# CC2530.net
KiCad netlist of a schematic drawn in Altium Designer
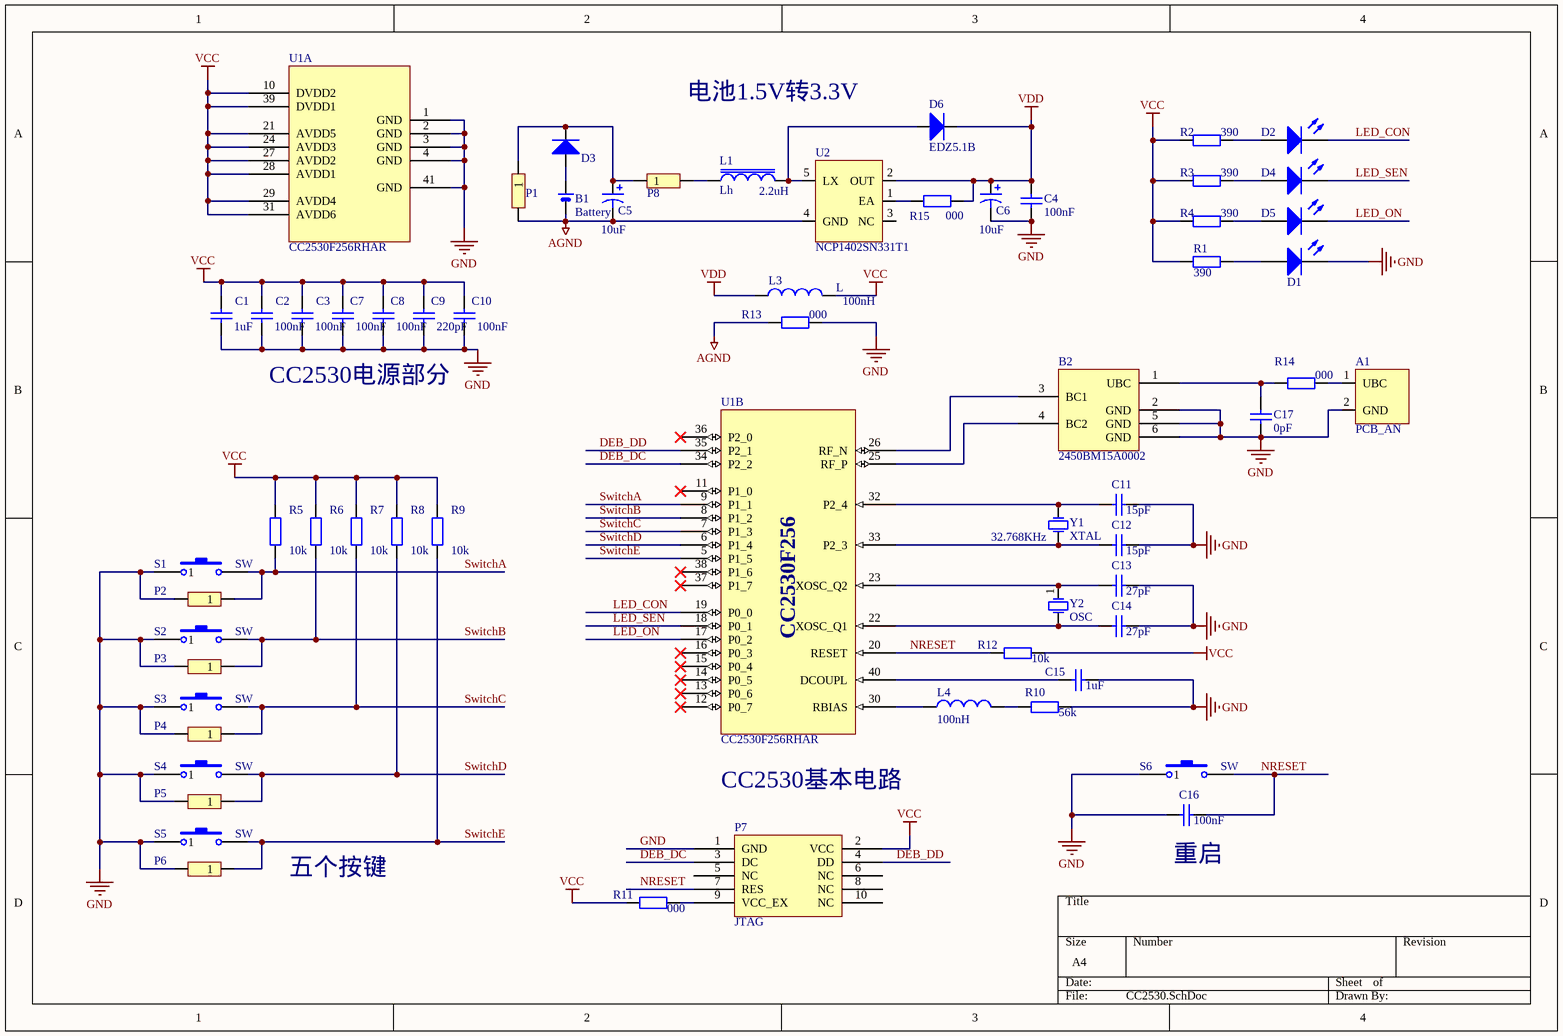
[diagram p0: CC2530.SchDoc]

(export (version "E")
  (design (tool "Eeschema 10.0.6"))
  (components
    (comp (ref "A1") (value "PCB_AN") (footprint "AN") (libsource (lib "Vote") (part "ANENTTA")))
    (comp (ref "B1") (value "Battery") (footprint "Battery") (libsource (lib "Vote") (part "Battery")))
    (comp (ref "B2")
      (value "2450BM15A0002")
      (footprint "SSOP 6")
      (libsource (lib "Vote") (part "2450BM15A0002"))
    )
    (comp (ref "C1")
      (value "1uF")
      (footprint "0603C")
      (fields (field (name "Comment") "C"))
      (libsource (lib "Vote") (part "C"))
    )
    (comp (ref "C2")
      (value "100nF")
      (footprint "0603C")
      (fields (field (name "Comment") "C"))
      (libsource (lib "Vote") (part "C"))
    )
    (comp (ref "C3")
      (value "100nF")
      (footprint "0603C")
      (fields (field (name "Comment") "C"))
      (libsource (lib "Vote") (part "C"))
    )
    (comp (ref "C4")
      (value "100nF")
      (footprint "0603C")
      (fields (field (name "Comment") "C"))
      (libsource (lib "Vote") (part "C"))
    )
    (comp (ref "C5")
      (value "10uF")
      (footprint "1210C")
      (fields (field (name "Comment") "DC"))
      (libsource (lib "Vote") (part "DC"))
    )
    (comp (ref "C6")
      (value "10uF")
      (footprint "1210C")
      (fields (field (name "Comment") "DC"))
      (libsource (lib "Vote") (part "DC"))
    )
    (comp (ref "C7")
      (value "100nF")
      (footprint "0603C")
      (fields (field (name "Comment") "C"))
      (libsource (lib "Vote") (part "C"))
    )
    (comp (ref "C8")
      (value "100nF")
      (footprint "0603C")
      (fields (field (name "Comment") "C"))
      (libsource (lib "Vote") (part "C"))
    )
    (comp (ref "C9")
      (value "220pF")
      (footprint "0603C")
      (fields (field (name "Comment") "C"))
      (libsource (lib "Vote") (part "C"))
    )
    (comp (ref "C10")
      (value "100nF")
      (footprint "0603C")
      (fields (field (name "Comment") "C"))
      (libsource (lib "Vote") (part "C"))
    )
    (comp (ref "C11")
      (value "15pF")
      (footprint "0603C")
      (fields (field (name "Comment") "C"))
      (libsource (lib "Vote") (part "C"))
    )
    (comp (ref "C12")
      (value "15pF")
      (footprint "0603C")
      (fields (field (name "Comment") "C"))
      (libsource (lib "Vote") (part "C"))
    )
    (comp (ref "C13")
      (value "27pF")
      (footprint "0603C")
      (fields (field (name "Comment") "C"))
      (libsource (lib "Vote") (part "C"))
    )
    (comp (ref "C14")
      (value "27pF")
      (footprint "0603C")
      (fields (field (name "Comment") "C"))
      (libsource (lib "Vote") (part "C"))
    )
    (comp (ref "C15")
      (value "1uF")
      (footprint "0603C")
      (fields (field (name "Comment") "C"))
      (libsource (lib "Vote") (part "C"))
    )
    (comp (ref "C16")
      (value "100nF")
      (footprint "0603C")
      (fields (field (name "Comment") "C"))
      (libsource (lib "Vote") (part "C"))
    )
    (comp (ref "C17")
      (value "0pF")
      (footprint "0603C")
      (fields (field (name "Comment") "C"))
      (libsource (lib "Vote") (part "C"))
    )
    (comp (ref "D1") (value "LED") (footprint "0603LED") (libsource (lib "Vote") (part "LED")))
    (comp (ref "D2") (value "LED") (footprint "0603LED") (libsource (lib "Vote") (part "LED")))
    (comp (ref "D3") (value "1N40005") (footprint "0805D") (libsource (lib "Vote") (part "1N40005")))
    (comp (ref "D4") (value "LED") (footprint "0603LED") (libsource (lib "Vote") (part "LED")))
    (comp (ref "D5") (value "LED") (footprint "0603LED") (libsource (lib "Vote") (part "LED")))
    (comp (ref "D6") (value "EDZ5.1B") (footprint "SOD-523") (libsource (lib "Vote") (part "1N40005")))
    (comp (ref "L1")
      (value "Lh")
      (footprint "E(1812)")
      (fields (field (name "ALTIUM_VALUE") "2.2uH"))
      (libsource (lib "Vote") (part "Lh"))
    )
    (comp (ref "L3")
      (value "L")
      (footprint "0603R")
      (fields (field (name "ALTIUM_VALUE") "100nH"))
      (libsource (lib "Vote") (part "L"))
    )
    (comp (ref "L4")
      (value "100nH")
      (footprint "0603R")
      (fields (field (name "Comment") "L"))
      (libsource (lib "Vote") (part "L"))
    )
    (comp (ref "P1") (value "Head 2*1") (footprint "HEAD 2*1") (libsource (lib "") (part "Head 2*1_1")))
    (comp (ref "P2") (value "Head 2*1") (footprint "HEAD 2*1") (libsource (lib "") (part "Head 2*1_2")))
    (comp (ref "P3") (value "Head 2*1") (footprint "HEAD 2*1") (libsource (lib "") (part "Head 2*1_2")))
    (comp (ref "P4") (value "Head 2*1") (footprint "HEAD 2*1") (libsource (lib "") (part "Head 2*1_2")))
    (comp (ref "P5") (value "Head 2*1") (footprint "HEAD 2*1") (libsource (lib "") (part "Head 2*1_2")))
    (comp (ref "P6") (value "Head 2*1") (footprint "HEAD 2*1") (libsource (lib "") (part "Head 2*1_2")))
    (comp (ref "P7") (value "JTAG") (footprint "HEAD 2*5") (libsource (lib "Vote") (part "JTAG")))
    (comp (ref "P8") (value "Head 2*1") (footprint "HEAD 2*1") (libsource (lib "Vote") (part "Head 2*1")))
    (comp (ref "R1")
      (value "390")
      (footprint "0603R")
      (fields (field (name "Comment") "R"))
      (libsource (lib "Vote") (part "R"))
    )
    (comp (ref "R2")
      (value "390")
      (footprint "0603R")
      (fields (field (name "Comment") "R"))
      (libsource (lib "Vote") (part "R"))
    )
    (comp (ref "R3")
      (value "390")
      (footprint "0603R")
      (fields (field (name "Comment") "R"))
      (libsource (lib "Vote") (part "R"))
    )
    (comp (ref "R4")
      (value "390")
      (footprint "0603R")
      (fields (field (name "Comment") "R"))
      (libsource (lib "Vote") (part "R"))
    )
    (comp (ref "R5")
      (value "10k")
      (footprint "0603R")
      (fields (field (name "Comment") "R"))
      (libsource (lib "") (part "R_1"))
    )
    (comp (ref "R6")
      (value "10k")
      (footprint "0603R")
      (fields (field (name "Comment") "R"))
      (libsource (lib "") (part "R_1"))
    )
    (comp (ref "R7")
      (value "10k")
      (footprint "0603R")
      (fields (field (name "Comment") "R"))
      (libsource (lib "") (part "R_1"))
    )
    (comp (ref "R8")
      (value "10k")
      (footprint "0603R")
      (fields (field (name "Comment") "R"))
      (libsource (lib "") (part "R_1"))
    )
    (comp (ref "R9")
      (value "10k")
      (footprint "0603R")
      (fields (field (name "Comment") "R"))
      (libsource (lib "") (part "R_1"))
    )
    (comp (ref "R10")
      (value "56k")
      (footprint "0603R")
      (fields (field (name "Comment") "R"))
      (libsource (lib "Vote") (part "R"))
    )
    (comp (ref "R11")
      (value "000")
      (footprint "0603R")
      (fields (field (name "Comment") "R"))
      (libsource (lib "Vote") (part "R"))
    )
    (comp (ref "R12")
      (value "10k")
      (footprint "0603R")
      (fields (field (name "Comment") "R"))
      (libsource (lib "Vote") (part "R"))
    )
    (comp (ref "R13")
      (value "000")
      (footprint "0603R")
      (fields (field (name "Comment") "R"))
      (libsource (lib "Vote") (part "R"))
    )
    (comp (ref "R14")
      (value "000")
      (footprint "0603R")
      (fields (field (name "Comment") "R"))
      (libsource (lib "Vote") (part "R"))
    )
    (comp (ref "R15")
      (value "000")
      (footprint "0603R")
      (fields (field (name "Comment") "R"))
      (libsource (lib "Vote") (part "R"))
    )
    (comp (ref "S1") (value "SW") (footprint "BUTTON") (libsource (lib "Vote") (part "SW")))
    (comp (ref "S2") (value "SW") (footprint "BUTTON") (libsource (lib "Vote") (part "SW")))
    (comp (ref "S3") (value "SW") (footprint "BUTTON") (libsource (lib "Vote") (part "SW")))
    (comp (ref "S4") (value "SW") (footprint "BUTTON") (libsource (lib "Vote") (part "SW")))
    (comp (ref "S5") (value "SW") (footprint "BUTTON") (libsource (lib "Vote") (part "SW")))
    (comp (ref "S6") (value "SW") (footprint "BUTTON") (libsource (lib "Vote") (part "SW")))
    (comp (ref "U1") (value "CC2530F256RHAR") (footprint "QPN 40") (libsource (lib "Vote") (part "CC2530")))
    (comp (ref "U2")
      (value "NCP1402SN331T1")
      (footprint "SOT23-5")
      (libsource (lib "Vote") (part "NCP1402SN331"))
    )
    (comp (ref "Y1")
      (value "XTAL")
      (footprint "1812")
      (fields (field (name "ALTIUM_VALUE") "32.768KHz"))
      (libsource (lib "Vote") (part "XTAL"))
    )
    (comp (ref "Y2") (value "OSC") (footprint "OSC") (libsource (lib "Vote") (part "OSC")))
  )
  (nets
    (net (code "1") (name "/DEB_DC") (class "Default")
      (node (ref "P7") (pin "3") (pinfunction "DC_3") (pintype "passive"))
      (node (ref "U1") (pin "34") (pinfunction "P2_2_34") (pintype "bidirectional"))
    )
    (net (code "2") (name "/DEB_DD") (class "Default")
      (node (ref "P7") (pin "4") (pinfunction "DD_4") (pintype "passive"))
      (node (ref "U1") (pin "35") (pinfunction "P2_1_35") (pintype "bidirectional"))
    )
    (net (code "3") (name "/LED_CON") (class "Default")
      (node (ref "D2") (pin "2") (pinfunction "K_2") (pintype "passive"))
      (node (ref "U1") (pin "19") (pinfunction "P0_0_19") (pintype "bidirectional"))
    )
    (net (code "4") (name "/LED_ON") (class "Default")
      (node (ref "D5") (pin "2") (pinfunction "K_2") (pintype "passive"))
      (node (ref "U1") (pin "17") (pinfunction "P0_2_17") (pintype "bidirectional"))
    )
    (net (code "5") (name "/LED_SEN") (class "Default")
      (node (ref "D4") (pin "2") (pinfunction "K_2") (pintype "passive"))
      (node (ref "U1") (pin "18") (pinfunction "P0_1_18") (pintype "bidirectional"))
    )
    (net (code "6") (name "/NRESET") (class "Default")
      (node (ref "C16") (pin "2") (pinfunction "2_2") (pintype "passive"))
      (node (ref "P7") (pin "7") (pinfunction "RES_7") (pintype "passive"))
      (node (ref "R12") (pin "2") (pinfunction "2_2") (pintype "passive"))
      (node (ref "S6") (pin "2") (pinfunction "2_2") (pintype "passive"))
      (node (ref "U1") (pin "20") (pinfunction "RESET_20") (pintype "input"))
    )
    (net (code "7") (name "/SwitchA") (class "Default")
      (node (ref "P2") (pin "1") (pinfunction "1_1") (pintype "passive"))
      (node (ref "R5") (pin "1") (pinfunction "1_1") (pintype "passive"))
      (node (ref "S1") (pin "2") (pinfunction "2_2") (pintype "passive"))
      (node (ref "U1") (pin "9") (pinfunction "P1_1_9") (pintype "bidirectional"))
    )
    (net (code "8") (name "/SwitchB") (class "Default")
      (node (ref "P3") (pin "1") (pinfunction "1_1") (pintype "passive"))
      (node (ref "R6") (pin "1") (pinfunction "1_1") (pintype "passive"))
      (node (ref "S2") (pin "2") (pinfunction "2_2") (pintype "passive"))
      (node (ref "U1") (pin "8") (pinfunction "P1_2_8") (pintype "bidirectional"))
    )
    (net (code "9") (name "/SwitchC") (class "Default")
      (node (ref "P4") (pin "1") (pinfunction "1_1") (pintype "passive"))
      (node (ref "R7") (pin "1") (pinfunction "1_1") (pintype "passive"))
      (node (ref "S3") (pin "2") (pinfunction "2_2") (pintype "passive"))
      (node (ref "U1") (pin "7") (pinfunction "P1_3_7") (pintype "bidirectional"))
    )
    (net (code "10") (name "/SwitchD") (class "Default")
      (node (ref "P5") (pin "1") (pinfunction "1_1") (pintype "passive"))
      (node (ref "R8") (pin "1") (pinfunction "1_1") (pintype "passive"))
      (node (ref "S4") (pin "2") (pinfunction "2_2") (pintype "passive"))
      (node (ref "U1") (pin "6") (pinfunction "P1_4_6") (pintype "bidirectional"))
    )
    (net (code "11") (name "/SwitchE") (class "Default")
      (node (ref "P6") (pin "1") (pinfunction "1_1") (pintype "passive"))
      (node (ref "R9") (pin "1") (pinfunction "1_1") (pintype "passive"))
      (node (ref "S5") (pin "2") (pinfunction "2_2") (pintype "passive"))
      (node (ref "U1") (pin "5") (pinfunction "P1_5_5") (pintype "bidirectional"))
    )
    (net (code "12") (name "AGND") (class "Default")
      (node (ref "B1") (pin "2") (pinfunction "OSC2_2") (pintype "passive"))
      (node (ref "C5") (pin "2") (pinfunction "2_2") (pintype "passive"))
      (node (ref "P1") (pin "2") (pinfunction "2_2") (pintype "passive"))
      (node (ref "R13") (pin "2") (pinfunction "2_2") (pintype "passive"))
      (node (ref "U2") (pin "4") (pinfunction "GND_4") (pintype "passive"))
    )
    (net (code "13") (name "GND") (class "Default")
      (node (ref "A1") (pin "2") (pinfunction "GND_2") (pintype "passive"))
      (node (ref "B2") (pin "2") (pinfunction "GND_2") (pintype "passive"))
      (node (ref "B2") (pin "5") (pinfunction "GND_5") (pintype "passive"))
      (node (ref "B2") (pin "6") (pinfunction "GND_6") (pintype "passive"))
      (node (ref "C1") (pin "2") (pinfunction "2_2") (pintype "passive"))
      (node (ref "C10") (pin "2") (pinfunction "2_2") (pintype "passive"))
      (node (ref "C11") (pin "2") (pinfunction "2_2") (pintype "passive"))
      (node (ref "C12") (pin "2") (pinfunction "2_2") (pintype "passive"))
      (node (ref "C13") (pin "2") (pinfunction "2_2") (pintype "passive"))
      (node (ref "C14") (pin "2") (pinfunction "2_2") (pintype "passive"))
      (node (ref "C15") (pin "2") (pinfunction "2_2") (pintype "passive"))
      (node (ref "C16") (pin "1") (pinfunction "1_1") (pintype "passive"))
      (node (ref "C17") (pin "2") (pinfunction "2_2") (pintype "passive"))
      (node (ref "C2") (pin "2") (pinfunction "2_2") (pintype "passive"))
      (node (ref "C3") (pin "2") (pinfunction "2_2") (pintype "passive"))
      (node (ref "C4") (pin "2") (pinfunction "2_2") (pintype "passive"))
      (node (ref "C6") (pin "2") (pinfunction "2_2") (pintype "passive"))
      (node (ref "C7") (pin "2") (pinfunction "2_2") (pintype "passive"))
      (node (ref "C8") (pin "2") (pinfunction "2_2") (pintype "passive"))
      (node (ref "C9") (pin "2") (pinfunction "2_2") (pintype "passive"))
      (node (ref "D1") (pin "2") (pinfunction "K_2") (pintype "passive"))
      (node (ref "P2") (pin "2") (pinfunction "2_2") (pintype "passive"))
      (node (ref "P3") (pin "2") (pinfunction "2_2") (pintype "passive"))
      (node (ref "P4") (pin "2") (pinfunction "2_2") (pintype "passive"))
      (node (ref "P5") (pin "2") (pinfunction "2_2") (pintype "passive"))
      (node (ref "P6") (pin "2") (pinfunction "2_2") (pintype "passive"))
      (node (ref "P7") (pin "1") (pinfunction "GND_1") (pintype "passive"))
      (node (ref "R10") (pin "1") (pinfunction "1_1") (pintype "passive"))
      (node (ref "R13") (pin "1") (pinfunction "1_1") (pintype "passive"))
      (node (ref "S1") (pin "1") (pinfunction "1_1") (pintype "passive"))
      (node (ref "S2") (pin "1") (pinfunction "1_1") (pintype "passive"))
      (node (ref "S3") (pin "1") (pinfunction "1_1") (pintype "passive"))
      (node (ref "S4") (pin "1") (pinfunction "1_1") (pintype "passive"))
      (node (ref "S5") (pin "1") (pinfunction "1_1") (pintype "passive"))
      (node (ref "S6") (pin "1") (pinfunction "1_1") (pintype "passive"))
      (node (ref "U1") (pin "1") (pinfunction "GND_1") (pintype "passive"))
      (node (ref "U1") (pin "2") (pinfunction "GND_2") (pintype "passive"))
      (node (ref "U1") (pin "3") (pinfunction "GND_3") (pintype "passive"))
      (node (ref "U1") (pin "4") (pinfunction "GND_4") (pintype "passive"))
      (node (ref "U1") (pin "41") (pinfunction "GND_41") (pintype "passive"))
    )
    (net (code "14") (name "Net-(A1-UBC)") (class "Default")
      (node (ref "A1") (pin "1") (pinfunction "UBC_1") (pintype "passive"))
      (node (ref "R14") (pin "1") (pinfunction "1_1") (pintype "passive"))
    )
    (net (code "15") (name "Net-(B1-OSC1)") (class "Default")
      (node (ref "B1") (pin "1") (pinfunction "OSC1_1") (pintype "passive"))
      (node (ref "D3") (pin "1") (pinfunction "A_1") (pintype "passive"))
    )
    (net (code "16") (name "Net-(B2-BC1)") (class "Default")
      (node (ref "B2") (pin "3") (pinfunction "BC1_3") (pintype "passive"))
      (node (ref "U1") (pin "26") (pinfunction "RF_N_26") (pintype "bidirectional"))
    )
    (net (code "17") (name "Net-(B2-BC2)") (class "Default")
      (node (ref "B2") (pin "4") (pinfunction "BC2_4") (pintype "passive"))
      (node (ref "U1") (pin "25") (pinfunction "RF_P_25") (pintype "bidirectional"))
    )
    (net (code "18") (name "Net-(B2-UBC)") (class "Default")
      (node (ref "B2") (pin "1") (pinfunction "UBC_1") (pintype "passive"))
      (node (ref "C17") (pin "1") (pinfunction "1_1") (pintype "passive"))
      (node (ref "R14") (pin "2") (pinfunction "2_2") (pintype "passive"))
    )
    (net (code "19") (name "Net-(D1-A)") (class "Default")
      (node (ref "D1") (pin "1") (pinfunction "A_1") (pintype "passive"))
      (node (ref "R1") (pin "1") (pinfunction "1_1") (pintype "passive"))
    )
    (net (code "20") (name "Net-(D2-A)") (class "Default")
      (node (ref "D2") (pin "1") (pinfunction "A_1") (pintype "passive"))
      (node (ref "R2") (pin "1") (pinfunction "1_1") (pintype "passive"))
    )
    (net (code "21") (name "Net-(D3-K)") (class "Default")
      (node (ref "C5") (pin "1") (pinfunction "1_1") (pintype "passive"))
      (node (ref "D3") (pin "2") (pinfunction "K_2") (pintype "passive"))
      (node (ref "P1") (pin "1") (pinfunction "1_1") (pintype "passive"))
      (node (ref "P8") (pin "1") (pinfunction "1_1") (pintype "passive"))
    )
    (net (code "22") (name "Net-(D4-A)") (class "Default")
      (node (ref "D4") (pin "1") (pinfunction "A_1") (pintype "passive"))
      (node (ref "R3") (pin "1") (pinfunction "1_1") (pintype "passive"))
    )
    (net (code "23") (name "Net-(D5-A)") (class "Default")
      (node (ref "D5") (pin "1") (pinfunction "A_1") (pintype "passive"))
      (node (ref "R4") (pin "1") (pinfunction "1_1") (pintype "passive"))
    )
    (net (code "24") (name "Net-(D6-A)") (class "Default")
      (node (ref "D6") (pin "1") (pinfunction "A_1") (pintype "passive"))
      (node (ref "L1") (pin "2") (pinfunction "2_2") (pintype "passive"))
      (node (ref "U2") (pin "5") (pinfunction "LX_5") (pintype "passive"))
    )
    (net (code "25") (name "Net-(L1-Pad1)") (class "Default")
      (node (ref "L1") (pin "1") (pinfunction "1_1") (pintype "passive"))
      (node (ref "P8") (pin "2") (pinfunction "2_2") (pintype "passive"))
    )
    (net (code "26") (name "Net-(L4-Pad2)") (class "Default")
      (node (ref "L4") (pin "2") (pinfunction "2_2") (pintype "passive"))
      (node (ref "R10") (pin "2") (pinfunction "2_2") (pintype "passive"))
    )
    (net (code "27") (name "Net-(P7-VCC_EX)") (class "Default")
      (node (ref "P7") (pin "9") (pinfunction "VCC_EX_9") (pintype "passive"))
      (node (ref "R11") (pin "1") (pinfunction "1_1") (pintype "passive"))
    )
    (net (code "28") (name "Net-(U1B-DCOUPL)") (class "Default")
      (node (ref "C15") (pin "1") (pinfunction "1_1") (pintype "passive"))
      (node (ref "U1") (pin "40") (pinfunction "DCOUPL_40") (pintype "input"))
    )
    (net (code "29") (name "Net-(U1B-P2_3)") (class "Default")
      (node (ref "C12") (pin "1") (pinfunction "1_1") (pintype "passive"))
      (node (ref "U1") (pin "33") (pinfunction "P2_3_33") (pintype "input"))
      (node (ref "Y1") (pin "1") (pinfunction "OSC1_1") (pintype "passive"))
    )
    (net (code "30") (name "Net-(U1B-P2_4)") (class "Default")
      (node (ref "C11") (pin "1") (pinfunction "1_1") (pintype "passive"))
      (node (ref "U1") (pin "32") (pinfunction "P2_4_32") (pintype "input"))
      (node (ref "Y1") (pin "2") (pinfunction "OSC2_2") (pintype "passive"))
    )
    (net (code "31") (name "Net-(U1B-RBIAS)") (class "Default")
      (node (ref "L4") (pin "1") (pinfunction "1_1") (pintype "passive"))
      (node (ref "U1") (pin "30") (pinfunction "RBIAS_30") (pintype "input"))
    )
    (net (code "32") (name "Net-(U1B-XOSC_Q1)") (class "Default")
      (node (ref "C14") (pin "1") (pinfunction "1_1") (pintype "passive"))
      (node (ref "U1") (pin "22") (pinfunction "XOSC_Q1_22") (pintype "input"))
      (node (ref "Y2") (pin "3") (pinfunction "OUT_3") (pintype "passive"))
    )
    (net (code "33") (name "Net-(U1B-XOSC_Q2)") (class "Default")
      (node (ref "C13") (pin "1") (pinfunction "1_1") (pintype "passive"))
      (node (ref "U1") (pin "23") (pinfunction "XOSC_Q2_23") (pintype "input"))
      (node (ref "Y2") (pin "1") (pinfunction "NC_1") (pintype "passive"))
    )
    (net (code "34") (name "Net-(U2-EA)") (class "Default")
      (node (ref "R15") (pin "2") (pinfunction "2_2") (pintype "passive"))
      (node (ref "U2") (pin "1") (pinfunction "EA_1") (pintype "passive"))
    )
    (net (code "35") (name "VCC") (class "Default")
      (node (ref "C1") (pin "1") (pinfunction "1_1") (pintype "passive"))
      (node (ref "C10") (pin "1") (pinfunction "1_1") (pintype "passive"))
      (node (ref "C2") (pin "1") (pinfunction "1_1") (pintype "passive"))
      (node (ref "C3") (pin "1") (pinfunction "1_1") (pintype "passive"))
      (node (ref "C7") (pin "1") (pinfunction "1_1") (pintype "passive"))
      (node (ref "C8") (pin "1") (pinfunction "1_1") (pintype "passive"))
      (node (ref "C9") (pin "1") (pinfunction "1_1") (pintype "passive"))
      (node (ref "L3") (pin "2") (pinfunction "2_2") (pintype "passive"))
      (node (ref "P7") (pin "2") (pinfunction "VCC_2") (pintype "passive"))
      (node (ref "R1") (pin "2") (pinfunction "2_2") (pintype "passive"))
      (node (ref "R11") (pin "2") (pinfunction "2_2") (pintype "passive"))
      (node (ref "R12") (pin "1") (pinfunction "1_1") (pintype "passive"))
      (node (ref "R2") (pin "2") (pinfunction "2_2") (pintype "passive"))
      (node (ref "R3") (pin "2") (pinfunction "2_2") (pintype "passive"))
      (node (ref "R4") (pin "2") (pinfunction "2_2") (pintype "passive"))
      (node (ref "R5") (pin "2") (pinfunction "2_2") (pintype "passive"))
      (node (ref "R6") (pin "2") (pinfunction "2_2") (pintype "passive"))
      (node (ref "R7") (pin "2") (pinfunction "2_2") (pintype "passive"))
      (node (ref "R8") (pin "2") (pinfunction "2_2") (pintype "passive"))
      (node (ref "R9") (pin "2") (pinfunction "2_2") (pintype "passive"))
      (node (ref "U1") (pin "10") (pinfunction "DVDD2_10") (pintype "passive"))
      (node (ref "U1") (pin "21") (pinfunction "AVDD5_21") (pintype "passive"))
      (node (ref "U1") (pin "24") (pinfunction "AVDD3_24") (pintype "passive"))
      (node (ref "U1") (pin "27") (pinfunction "AVDD2_27") (pintype "passive"))
      (node (ref "U1") (pin "28") (pinfunction "AVDD1_28") (pintype "passive"))
      (node (ref "U1") (pin "29") (pinfunction "AVDD4_29") (pintype "passive"))
      (node (ref "U1") (pin "31") (pinfunction "AVDD6_31") (pintype "passive"))
      (node (ref "U1") (pin "39") (pinfunction "DVDD1_39") (pintype "passive"))
    )
    (net (code "36") (name "VDD") (class "Default")
      (node (ref "C4") (pin "1") (pinfunction "1_1") (pintype "passive"))
      (node (ref "C6") (pin "1") (pinfunction "1_1") (pintype "passive"))
      (node (ref "D6") (pin "2") (pinfunction "K_2") (pintype "passive"))
      (node (ref "L3") (pin "1") (pinfunction "1_1") (pintype "passive"))
      (node (ref "R15") (pin "1") (pinfunction "1_1") (pintype "passive"))
      (node (ref "U2") (pin "2") (pinfunction "OUT_2") (pintype "passive"))
    )
    (net (code "37") (name "unconnected-(P7-NC-Pad5)") (class "Default")
      (node (ref "P7") (pin "5") (pinfunction "NC_5") (pintype "passive"))
    )
    (net (code "38") (name "unconnected-(P7-NC-Pad6)") (class "Default")
      (node (ref "P7") (pin "6") (pinfunction "NC_6") (pintype "passive"))
    )
    (net (code "39") (name "unconnected-(P7-NC-Pad8)") (class "Default")
      (node (ref "P7") (pin "8") (pinfunction "NC_8") (pintype "passive"))
    )
    (net (code "40") (name "unconnected-(P7-NC-Pad10)") (class "Default")
      (node (ref "P7") (pin "10") (pinfunction "NC_10") (pintype "passive"))
    )
    (net (code "41") (name "unconnected-(U1B-P0_3-Pad16)") (class "Default")
      (node (ref "U1") (pin "16") (pinfunction "P0_3_16") (pintype "bidirectional+no_connect"))
    )
    (net (code "42") (name "unconnected-(U1B-P0_4-Pad15)") (class "Default")
      (node (ref "U1") (pin "15") (pinfunction "P0_4_15") (pintype "bidirectional+no_connect"))
    )
    (net (code "43") (name "unconnected-(U1B-P0_5-Pad14)") (class "Default")
      (node (ref "U1") (pin "14") (pinfunction "P0_5_14") (pintype "bidirectional+no_connect"))
    )
    (net (code "44") (name "unconnected-(U1B-P0_6-Pad13)") (class "Default")
      (node (ref "U1") (pin "13") (pinfunction "P0_6_13") (pintype "bidirectional+no_connect"))
    )
    (net (code "45") (name "unconnected-(U1B-P0_7-Pad12)") (class "Default")
      (node (ref "U1") (pin "12") (pinfunction "P0_7_12") (pintype "bidirectional+no_connect"))
    )
    (net (code "46") (name "unconnected-(U1B-P1_0-Pad11)") (class "Default")
      (node (ref "U1") (pin "11") (pinfunction "P1_0_11") (pintype "bidirectional+no_connect"))
    )
    (net (code "47") (name "unconnected-(U1B-P1_6-Pad38)") (class "Default")
      (node (ref "U1") (pin "38") (pinfunction "P1_6_38") (pintype "bidirectional+no_connect"))
    )
    (net (code "48") (name "unconnected-(U1B-P1_7-Pad37)") (class "Default")
      (node (ref "U1") (pin "37") (pinfunction "P1_7_37") (pintype "bidirectional+no_connect"))
    )
    (net (code "49") (name "unconnected-(U1B-P2_0-Pad36)") (class "Default")
      (node (ref "U1") (pin "36") (pinfunction "P2_0_36") (pintype "bidirectional+no_connect"))
    )
    (net (code "50") (name "unconnected-(U2-NC-Pad3)") (class "Default")
      (node (ref "U2") (pin "3") (pinfunction "NC_3") (pintype "passive"))
    )
  )
)
